# Jack_In.net
KiCad netlist of a schematic drawn in Altium Designer
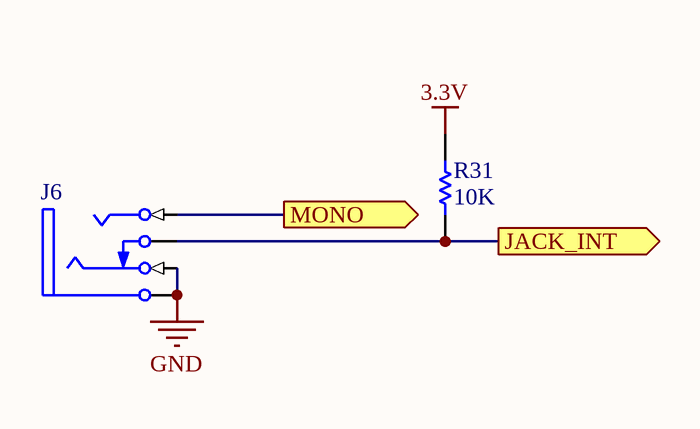
[diagram p0: Jack_In.SchDoc]

(export (version "E")
  (design (tool "Eeschema 10.0.6"))
  (components
    (comp (ref "J6")
      (value "Phonejack3 RN")
      (footprint "MHDR1X4")
      (description "Jack Socket, 1/4\" [6.5mm], Thru-Hole, Vertical, 3-Conductor with Tip open & Ring closed")
      (fields (field (name "PUBLISHER") "Altium Limited"))
      (libsource (lib "Miscellaneous Connectors") (part "Phonejack3 RN"))
    )
    (comp (ref "R31")
      (value "10K")
      (footprint "AXIAL-0.3")
      (description "Resistor")
      (fields (field (name "Comment") "Res1") (field (name "PUBLISHER") "Altium Limited"))
      (libsource (lib "Miscellaneous Devices") (part "Res1"))
    )
  )
  (nets
    (net (code "1") (name "/JACK_INT") (class "Default")
      (node (ref "J6") (pin "4") (pinfunction "RN_4") (pintype "passive"))
      (node (ref "R31") (pin "1") (pinfunction "1_1") (pintype "passive"))
    )
    (net (code "2") (name "/MONO") (class "Default")
      (node (ref "J6") (pin "1") (pinfunction "T_1") (pintype "input"))
    )
    (net (code "3") (name "3.3V") (class "Default")
      (node (ref "R31") (pin "2") (pinfunction "2_2") (pintype "passive"))
    )
    (net (code "4") (name "GND") (class "Default")
      (node (ref "J6") (pin "3") (pinfunction "R_3") (pintype "input"))
      (node (ref "J6") (pin "5") (pinfunction "S_5") (pintype "power_in"))
    )
  )
)
